# indicator.net
KiCad netlist of a schematic drawn in EAGLE
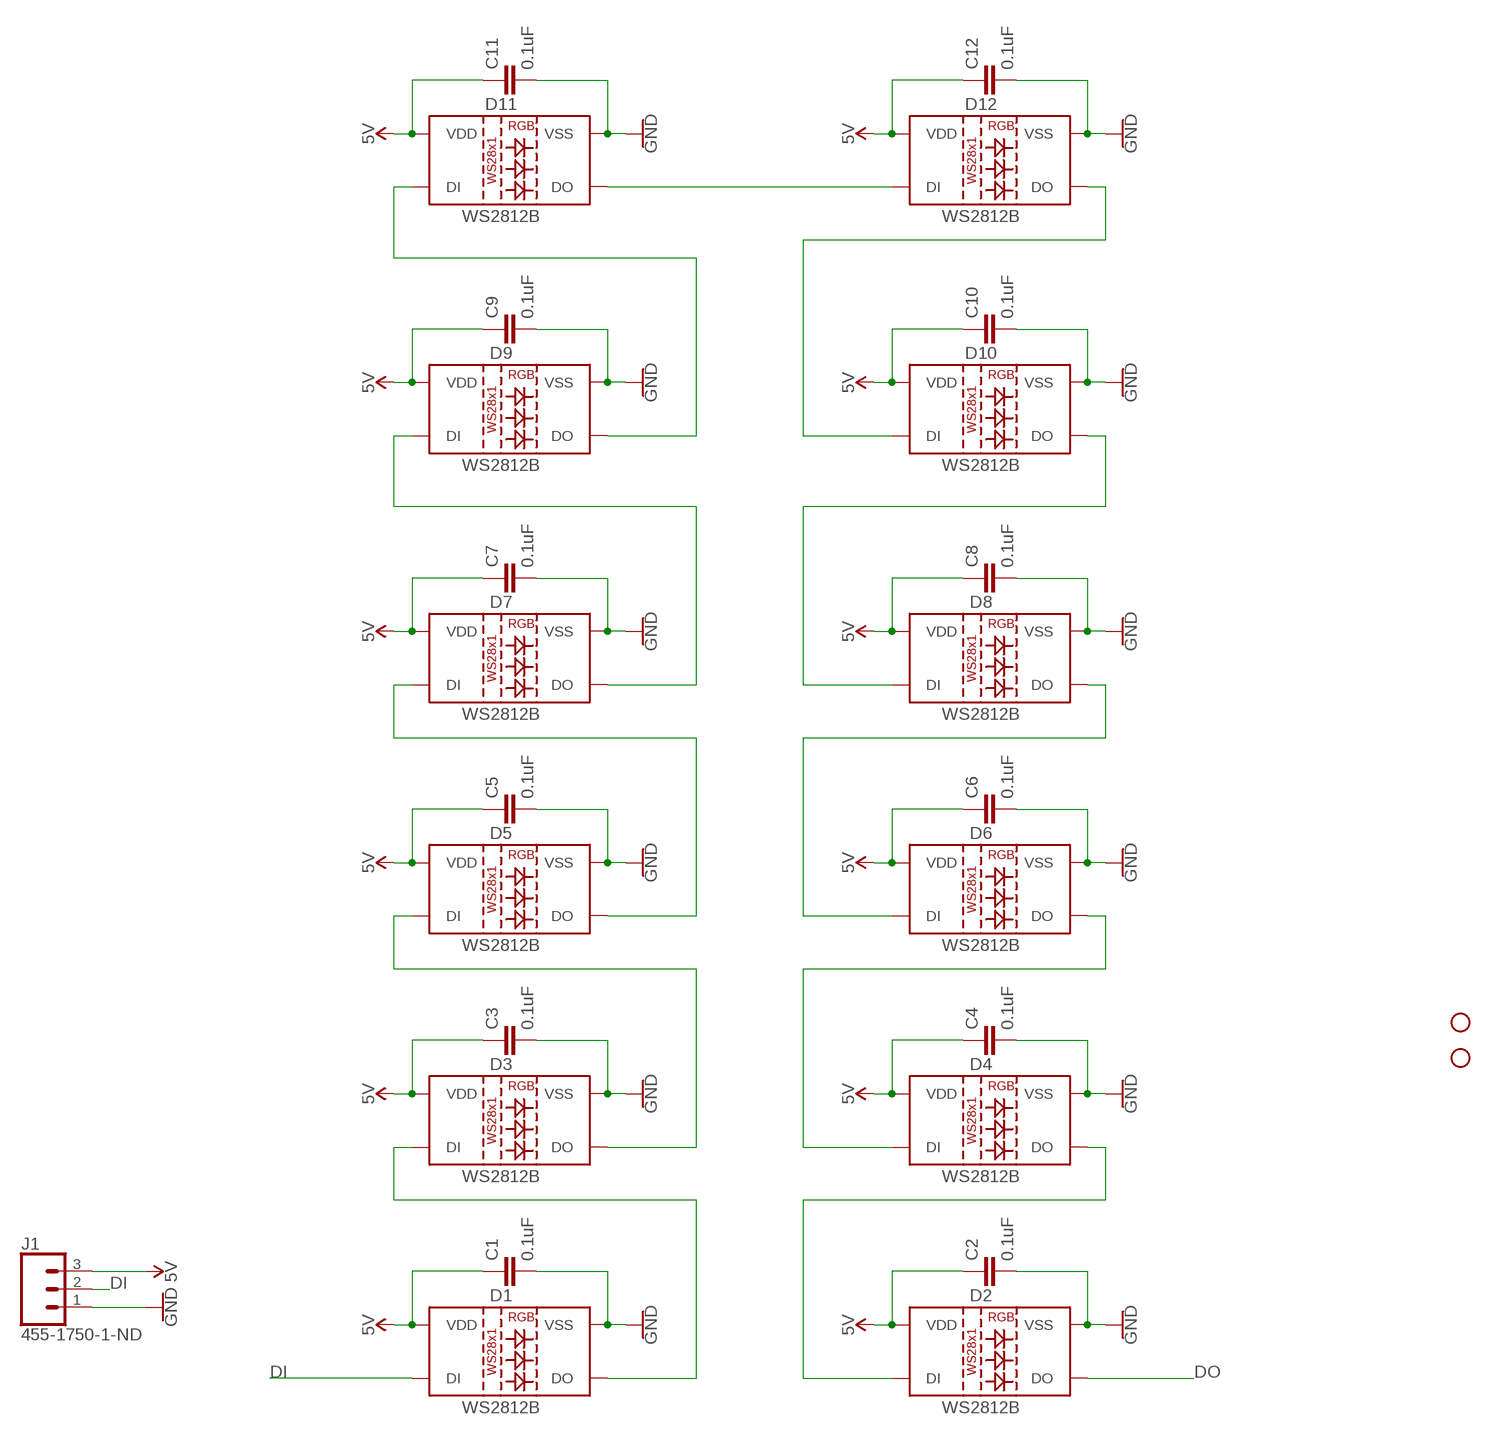
[diagram p0: schematic, sheet 1]

(export (version "E")
  (design (tool "Eeschema 10.0.6"))
  (components
    (comp (ref "C1")
      (value "0.1uF")
      (footprint "eagle-import:0603")
      (libsource (lib "eagle-import") (part "0.1UF-0603-25V-(+80/-20%)"))
    )
    (comp (ref "C2")
      (value "0.1uF")
      (footprint "eagle-import:0603")
      (libsource (lib "eagle-import") (part "0.1UF-0603-25V-(+80/-20%)"))
    )
    (comp (ref "C3")
      (value "0.1uF")
      (footprint "eagle-import:0603")
      (libsource (lib "eagle-import") (part "0.1UF-0603-25V-(+80/-20%)"))
    )
    (comp (ref "C4")
      (value "0.1uF")
      (footprint "eagle-import:0603")
      (libsource (lib "eagle-import") (part "0.1UF-0603-25V-(+80/-20%)"))
    )
    (comp (ref "C5")
      (value "0.1uF")
      (footprint "eagle-import:0603")
      (libsource (lib "eagle-import") (part "0.1UF-0603-25V-(+80/-20%)"))
    )
    (comp (ref "C6")
      (value "0.1uF")
      (footprint "eagle-import:0603")
      (libsource (lib "eagle-import") (part "0.1UF-0603-25V-(+80/-20%)"))
    )
    (comp (ref "C7")
      (value "0.1uF")
      (footprint "eagle-import:0603")
      (libsource (lib "eagle-import") (part "0.1UF-0603-25V-(+80/-20%)"))
    )
    (comp (ref "C8")
      (value "0.1uF")
      (footprint "eagle-import:0603")
      (libsource (lib "eagle-import") (part "0.1UF-0603-25V-(+80/-20%)"))
    )
    (comp (ref "C9")
      (value "0.1uF")
      (footprint "eagle-import:0603")
      (libsource (lib "eagle-import") (part "0.1UF-0603-25V-(+80/-20%)"))
    )
    (comp (ref "C10")
      (value "0.1uF")
      (footprint "eagle-import:0603")
      (libsource (lib "eagle-import") (part "0.1UF-0603-25V-(+80/-20%)"))
    )
    (comp (ref "C11")
      (value "0.1uF")
      (footprint "eagle-import:0603")
      (libsource (lib "eagle-import") (part "0.1UF-0603-25V-(+80/-20%)"))
    )
    (comp (ref "C12")
      (value "0.1uF")
      (footprint "eagle-import:0603")
      (libsource (lib "eagle-import") (part "0.1UF-0603-25V-(+80/-20%)"))
    )
    (comp (ref "D1")
      (value "WS2812B")
      (footprint "eagle-import:WS2812B")
      (libsource (lib "eagle-import") (part "WS2812B"))
    )
    (comp (ref "D2")
      (value "WS2812B")
      (footprint "eagle-import:WS2812B")
      (libsource (lib "eagle-import") (part "WS2812B"))
    )
    (comp (ref "D3")
      (value "WS2812B")
      (footprint "eagle-import:WS2812B")
      (libsource (lib "eagle-import") (part "WS2812B"))
    )
    (comp (ref "D4")
      (value "WS2812B")
      (footprint "eagle-import:WS2812B")
      (libsource (lib "eagle-import") (part "WS2812B"))
    )
    (comp (ref "D5")
      (value "WS2812B")
      (footprint "eagle-import:WS2812B")
      (libsource (lib "eagle-import") (part "WS2812B"))
    )
    (comp (ref "D6")
      (value "WS2812B")
      (footprint "eagle-import:WS2812B")
      (libsource (lib "eagle-import") (part "WS2812B"))
    )
    (comp (ref "D7")
      (value "WS2812B")
      (footprint "eagle-import:WS2812B")
      (libsource (lib "eagle-import") (part "WS2812B"))
    )
    (comp (ref "D8")
      (value "WS2812B")
      (footprint "eagle-import:WS2812B")
      (libsource (lib "eagle-import") (part "WS2812B"))
    )
    (comp (ref "D9")
      (value "WS2812B")
      (footprint "eagle-import:WS2812B")
      (libsource (lib "eagle-import") (part "WS2812B"))
    )
    (comp (ref "D10")
      (value "WS2812B")
      (footprint "eagle-import:WS2812B")
      (libsource (lib "eagle-import") (part "WS2812B"))
    )
    (comp (ref "D11")
      (value "WS2812B")
      (footprint "eagle-import:WS2812B")
      (libsource (lib "eagle-import") (part "WS2812B"))
    )
    (comp (ref "D12")
      (value "WS2812B")
      (footprint "eagle-import:WS2812B")
      (libsource (lib "eagle-import") (part "WS2812B"))
    )
    (comp (ref "H1")
      (value "STAND-OFF")
      (footprint "eagle-import:STAND-OFF")
      (libsource (lib "eagle-import") (part "STAND-OFF"))
    )
    (comp (ref "H2")
      (value "STAND-OFF")
      (footprint "eagle-import:STAND-OFF")
      (libsource (lib "eagle-import") (part "STAND-OFF"))
    )
    (comp (ref "J1")
      (value "455-1750-1-ND")
      (footprint "eagle-import:1X03")
      (libsource (lib "eagle-import") (part "CONN_03"))
    )
  )
  (nets
    (net (code "1") (name "/DI") (class "Default")
      (node (ref "D1") (pin "4") (pinfunction "DI_4") (pintype "bidirectional"))
      (node (ref "J1") (pin "2") (pinfunction "2_2") (pintype "passive"))
    )
    (net (code "2") (name "/DO") (class "Default")
      (node (ref "D2") (pin "2") (pinfunction "DO_2") (pintype "bidirectional"))
    )
    (net (code "3") (name "5V") (class "Default")
      (node (ref "C1") (pin "1") (pinfunction "1_1") (pintype "passive"))
      (node (ref "C10") (pin "1") (pinfunction "1_1") (pintype "passive"))
      (node (ref "C11") (pin "1") (pinfunction "1_1") (pintype "passive"))
      (node (ref "C12") (pin "1") (pinfunction "1_1") (pintype "passive"))
      (node (ref "C2") (pin "1") (pinfunction "1_1") (pintype "passive"))
      (node (ref "C3") (pin "1") (pinfunction "1_1") (pintype "passive"))
      (node (ref "C4") (pin "1") (pinfunction "1_1") (pintype "passive"))
      (node (ref "C5") (pin "1") (pinfunction "1_1") (pintype "passive"))
      (node (ref "C6") (pin "1") (pinfunction "1_1") (pintype "passive"))
      (node (ref "C7") (pin "1") (pinfunction "1_1") (pintype "passive"))
      (node (ref "C8") (pin "1") (pinfunction "1_1") (pintype "passive"))
      (node (ref "C9") (pin "1") (pinfunction "1_1") (pintype "passive"))
      (node (ref "D1") (pin "1") (pinfunction "VDD_1") (pintype "bidirectional"))
      (node (ref "D10") (pin "1") (pinfunction "VDD_1") (pintype "bidirectional"))
      (node (ref "D11") (pin "1") (pinfunction "VDD_1") (pintype "bidirectional"))
      (node (ref "D12") (pin "1") (pinfunction "VDD_1") (pintype "bidirectional"))
      (node (ref "D2") (pin "1") (pinfunction "VDD_1") (pintype "bidirectional"))
      (node (ref "D3") (pin "1") (pinfunction "VDD_1") (pintype "bidirectional"))
      (node (ref "D4") (pin "1") (pinfunction "VDD_1") (pintype "bidirectional"))
      (node (ref "D5") (pin "1") (pinfunction "VDD_1") (pintype "bidirectional"))
      (node (ref "D6") (pin "1") (pinfunction "VDD_1") (pintype "bidirectional"))
      (node (ref "D7") (pin "1") (pinfunction "VDD_1") (pintype "bidirectional"))
      (node (ref "D8") (pin "1") (pinfunction "VDD_1") (pintype "bidirectional"))
      (node (ref "D9") (pin "1") (pinfunction "VDD_1") (pintype "bidirectional"))
      (node (ref "J1") (pin "3") (pinfunction "3_3") (pintype "passive"))
    )
    (net (code "4") (name "GND") (class "Default")
      (node (ref "C1") (pin "2") (pinfunction "2_2") (pintype "passive"))
      (node (ref "C10") (pin "2") (pinfunction "2_2") (pintype "passive"))
      (node (ref "C11") (pin "2") (pinfunction "2_2") (pintype "passive"))
      (node (ref "C12") (pin "2") (pinfunction "2_2") (pintype "passive"))
      (node (ref "C2") (pin "2") (pinfunction "2_2") (pintype "passive"))
      (node (ref "C3") (pin "2") (pinfunction "2_2") (pintype "passive"))
      (node (ref "C4") (pin "2") (pinfunction "2_2") (pintype "passive"))
      (node (ref "C5") (pin "2") (pinfunction "2_2") (pintype "passive"))
      (node (ref "C6") (pin "2") (pinfunction "2_2") (pintype "passive"))
      (node (ref "C7") (pin "2") (pinfunction "2_2") (pintype "passive"))
      (node (ref "C8") (pin "2") (pinfunction "2_2") (pintype "passive"))
      (node (ref "C9") (pin "2") (pinfunction "2_2") (pintype "passive"))
      (node (ref "D1") (pin "3") (pinfunction "VSS_3") (pintype "bidirectional"))
      (node (ref "D10") (pin "3") (pinfunction "VSS_3") (pintype "bidirectional"))
      (node (ref "D11") (pin "3") (pinfunction "VSS_3") (pintype "bidirectional"))
      (node (ref "D12") (pin "3") (pinfunction "VSS_3") (pintype "bidirectional"))
      (node (ref "D2") (pin "3") (pinfunction "VSS_3") (pintype "bidirectional"))
      (node (ref "D3") (pin "3") (pinfunction "VSS_3") (pintype "bidirectional"))
      (node (ref "D4") (pin "3") (pinfunction "VSS_3") (pintype "bidirectional"))
      (node (ref "D5") (pin "3") (pinfunction "VSS_3") (pintype "bidirectional"))
      (node (ref "D6") (pin "3") (pinfunction "VSS_3") (pintype "bidirectional"))
      (node (ref "D7") (pin "3") (pinfunction "VSS_3") (pintype "bidirectional"))
      (node (ref "D8") (pin "3") (pinfunction "VSS_3") (pintype "bidirectional"))
      (node (ref "D9") (pin "3") (pinfunction "VSS_3") (pintype "bidirectional"))
      (node (ref "J1") (pin "1") (pinfunction "1_1") (pintype "passive"))
    )
    (net (code "5") (name "Net-(D1-DO)") (class "Default")
      (node (ref "D1") (pin "2") (pinfunction "DO_2") (pintype "bidirectional"))
      (node (ref "D3") (pin "4") (pinfunction "DI_4") (pintype "bidirectional"))
    )
    (net (code "6") (name "Net-(D2-DI)") (class "Default")
      (node (ref "D2") (pin "4") (pinfunction "DI_4") (pintype "bidirectional"))
      (node (ref "D4") (pin "2") (pinfunction "DO_2") (pintype "bidirectional"))
    )
    (net (code "7") (name "Net-(D3-DO)") (class "Default")
      (node (ref "D3") (pin "2") (pinfunction "DO_2") (pintype "bidirectional"))
      (node (ref "D5") (pin "4") (pinfunction "DI_4") (pintype "bidirectional"))
    )
    (net (code "8") (name "Net-(D4-DI)") (class "Default")
      (node (ref "D4") (pin "4") (pinfunction "DI_4") (pintype "bidirectional"))
      (node (ref "D6") (pin "2") (pinfunction "DO_2") (pintype "bidirectional"))
    )
    (net (code "9") (name "Net-(D5-DO)") (class "Default")
      (node (ref "D5") (pin "2") (pinfunction "DO_2") (pintype "bidirectional"))
      (node (ref "D7") (pin "4") (pinfunction "DI_4") (pintype "bidirectional"))
    )
    (net (code "10") (name "Net-(D6-DI)") (class "Default")
      (node (ref "D6") (pin "4") (pinfunction "DI_4") (pintype "bidirectional"))
      (node (ref "D8") (pin "2") (pinfunction "DO_2") (pintype "bidirectional"))
    )
    (net (code "11") (name "Net-(D7-DO)") (class "Default")
      (node (ref "D7") (pin "2") (pinfunction "DO_2") (pintype "bidirectional"))
      (node (ref "D9") (pin "4") (pinfunction "DI_4") (pintype "bidirectional"))
    )
    (net (code "12") (name "Net-(D10-DI)") (class "Default")
      (node (ref "D10") (pin "4") (pinfunction "DI_4") (pintype "bidirectional"))
      (node (ref "D12") (pin "2") (pinfunction "DO_2") (pintype "bidirectional"))
    )
    (net (code "13") (name "Net-(D10-DO)") (class "Default")
      (node (ref "D10") (pin "2") (pinfunction "DO_2") (pintype "bidirectional"))
      (node (ref "D8") (pin "4") (pinfunction "DI_4") (pintype "bidirectional"))
    )
    (net (code "14") (name "Net-(D11-DI)") (class "Default")
      (node (ref "D11") (pin "4") (pinfunction "DI_4") (pintype "bidirectional"))
      (node (ref "D9") (pin "2") (pinfunction "DO_2") (pintype "bidirectional"))
    )
    (net (code "15") (name "Net-(D11-DO)") (class "Default")
      (node (ref "D11") (pin "2") (pinfunction "DO_2") (pintype "bidirectional"))
      (node (ref "D12") (pin "4") (pinfunction "DI_4") (pintype "bidirectional"))
    )
  )
)
